# Sequencer-V02-025.net
KiCad netlist of a schematic drawn in EAGLE
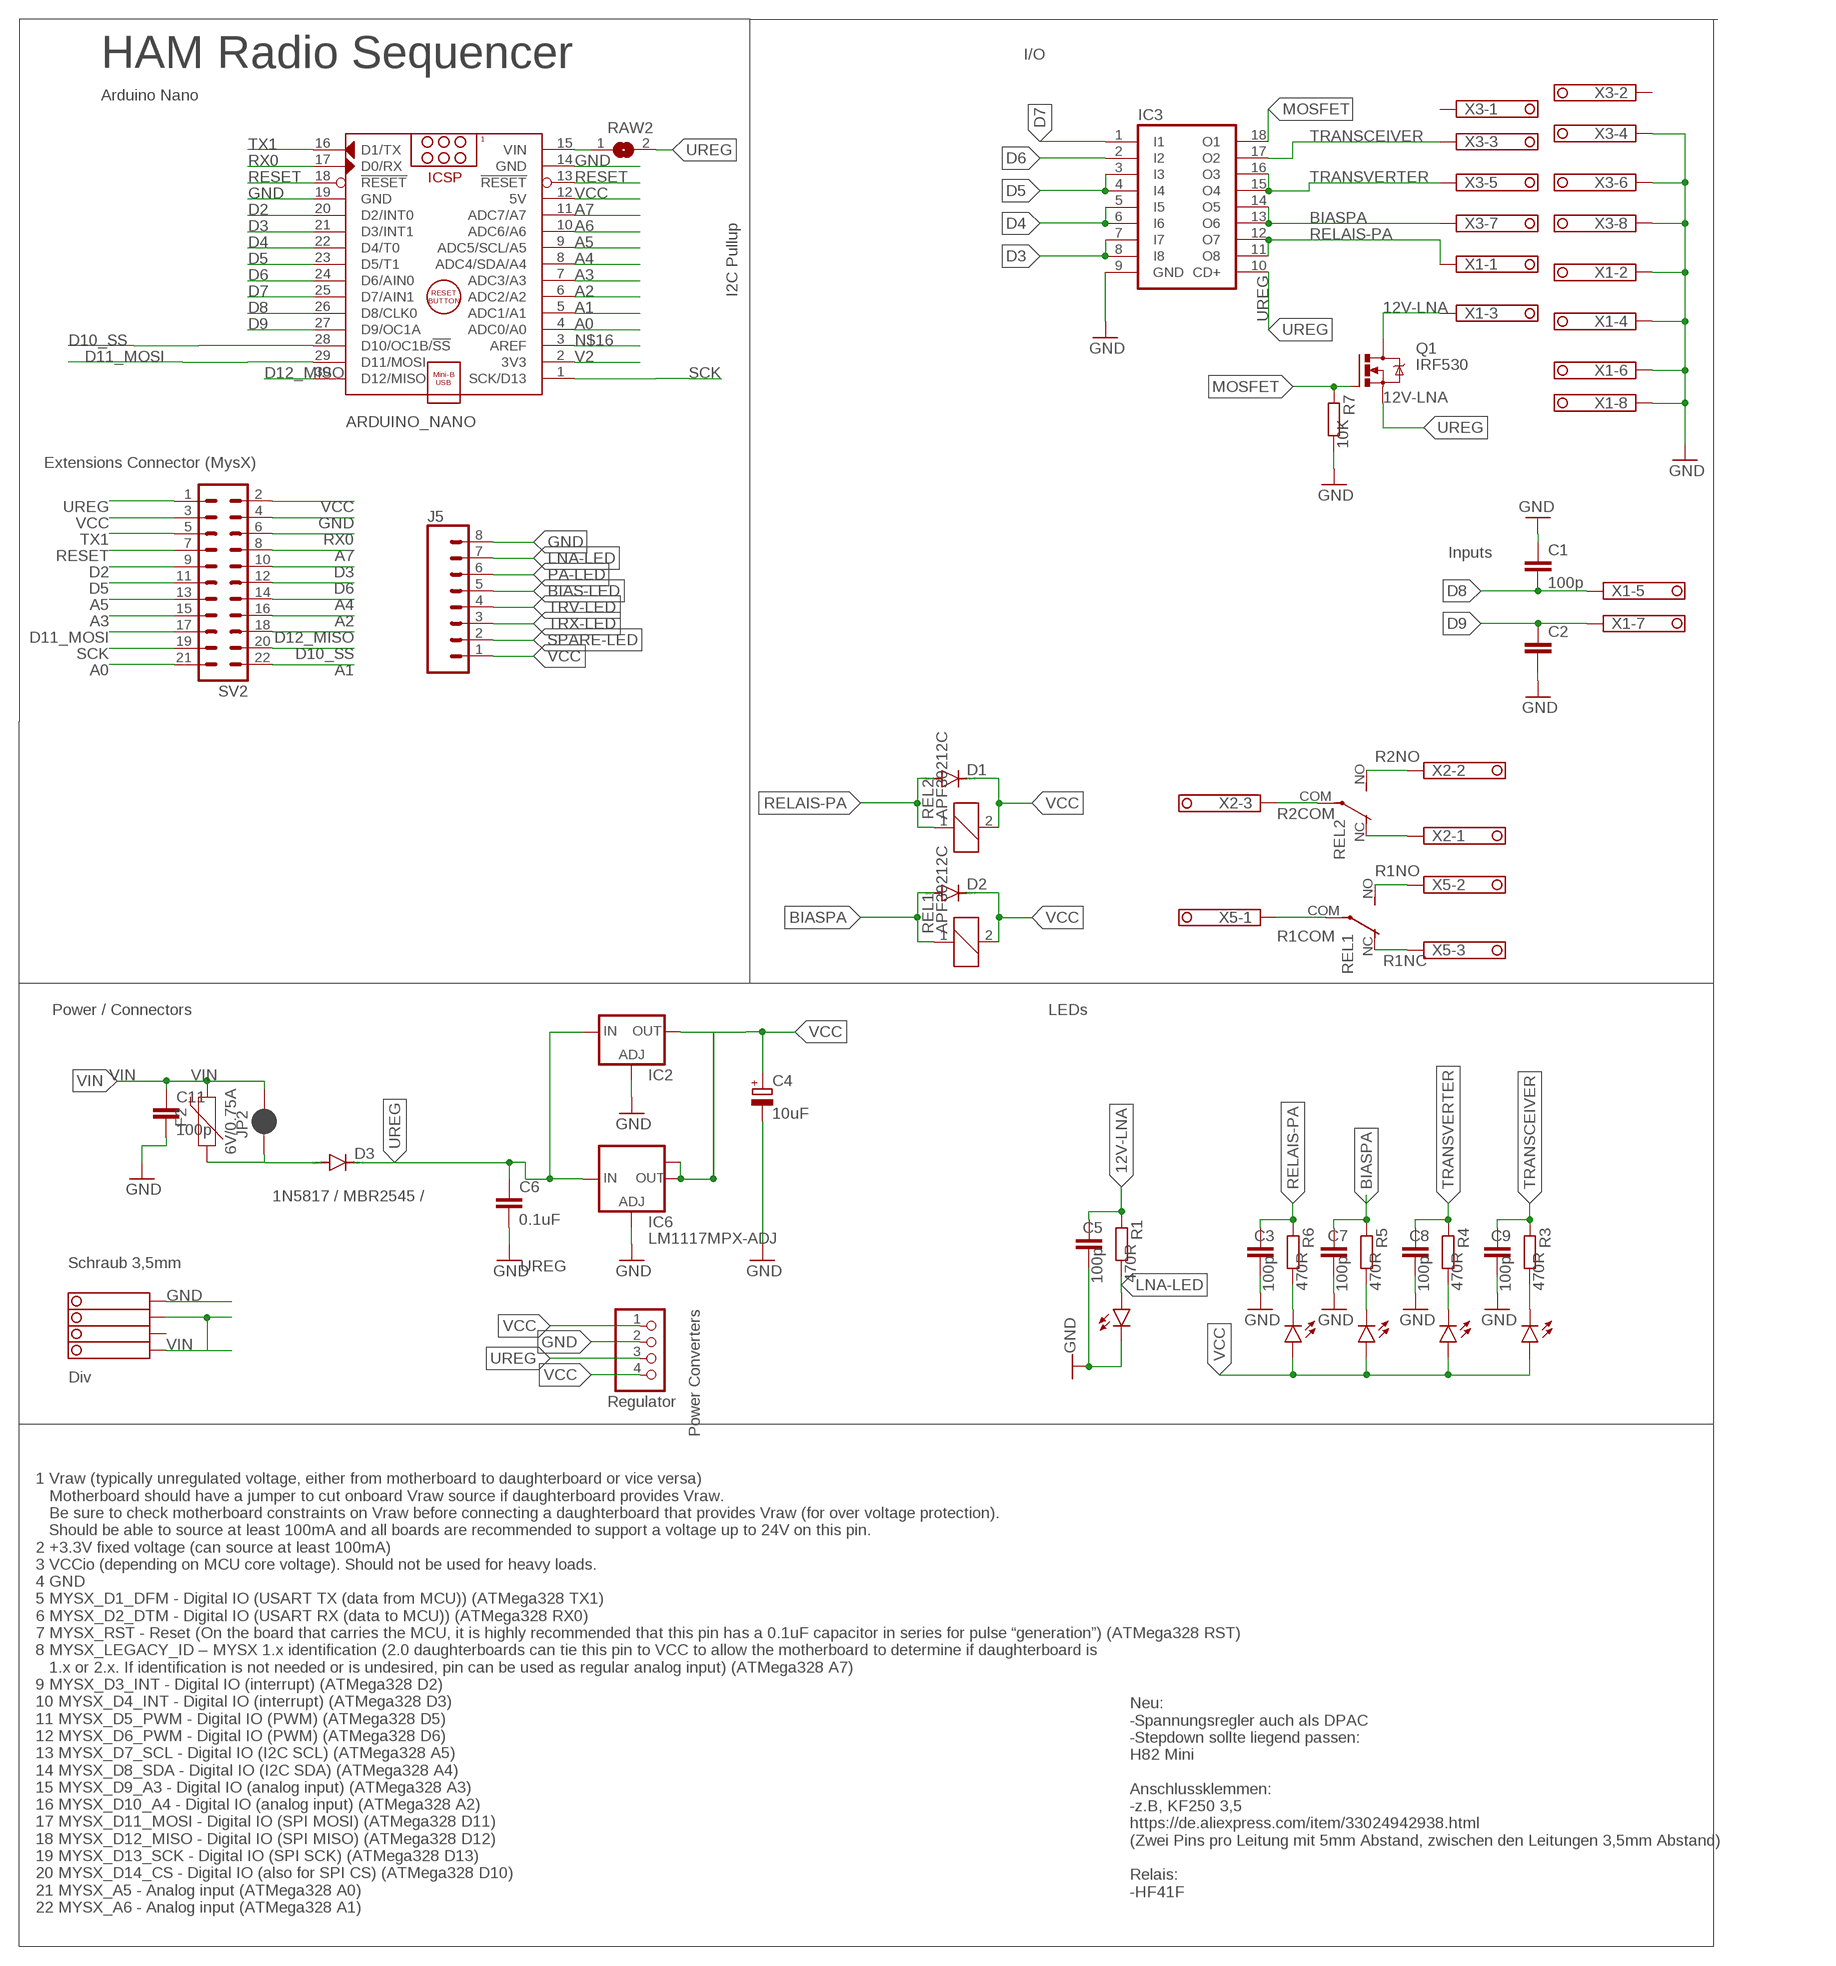
[diagram p0: schematic, sheet 1]

(export (version "E")
  (design (tool "Eeschema 10.0.6"))
  (components
    (comp (ref "ARDUINO_NANO")
      (value "ARDUINO_NANO_OHNE-BOHR")
      (footprint "eagle-import:ARDUINO_NANO")
      (libsource (lib "eagle-import") (part "ARDUINO_NANO_OHNE-BOHR"))
    )
    (comp (ref "C1")
      (value "100p")
      (footprint "eagle-import:C025-025X050")
      (libsource (lib "eagle-import") (part "C-EU025-025X050"))
    )
    (comp (ref "C2")
      (value "C-EU025-025X050")
      (footprint "eagle-import:C025-025X050")
      (libsource (lib "eagle-import") (part "C-EU025-025X050"))
    )
    (comp (ref "C3")
      (value "100p")
      (footprint "eagle-import:C025-025X050")
      (libsource (lib "eagle-import") (part "C-EU025-025X050"))
    )
    (comp (ref "C4")
      (value "10uF")
      (footprint "eagle-import:E3,5-8")
      (libsource (lib "eagle-import") (part "CPOL-EUE3.5-8"))
    )
    (comp (ref "C5")
      (value "100p")
      (footprint "eagle-import:C025-025X050")
      (libsource (lib "eagle-import") (part "C-EU025-025X050"))
    )
    (comp (ref "C6")
      (value "0.1uF")
      (footprint "eagle-import:C050-024X044")
      (libsource (lib "eagle-import") (part "C-EU050-024X044"))
    )
    (comp (ref "C7")
      (value "100p")
      (footprint "eagle-import:C025-025X050")
      (libsource (lib "eagle-import") (part "C-EU025-025X050"))
    )
    (comp (ref "C8")
      (value "100p")
      (footprint "eagle-import:C025-025X050")
      (libsource (lib "eagle-import") (part "C-EU025-025X050"))
    )
    (comp (ref "C9")
      (value "100p")
      (footprint "eagle-import:C025-025X050")
      (libsource (lib "eagle-import") (part "C-EU025-025X050"))
    )
    (comp (ref "C11")
      (value "100p")
      (footprint "eagle-import:C025-025X050")
      (libsource (lib "eagle-import") (part "C-EU025-025X050"))
    )
    (comp (ref "D1")
      (value "DIODE-D-2.5")
      (footprint "eagle-import:D-2.5")
      (libsource (lib "eagle-import") (part "DIODE-D-2.5"))
    )
    (comp (ref "D2")
      (value "DIODE-D-2.5")
      (footprint "eagle-import:D-2.5")
      (libsource (lib "eagle-import") (part "DIODE-D-2.5"))
    )
    (comp (ref "D3")
      (value "1N5817 / MBR2545 /")
      (footprint "eagle-import:D-7.5")
      (libsource (lib "eagle-import") (part "DIODE-D-7.5"))
    )
    (comp (ref "F2")
      (value "6V/0.75A")
      (footprint "eagle-import:1206")
      (libsource (lib "eagle-import") (part "PPTC_THREE-QUARTER-AMP"))
    )
    (comp (ref "IC2")
      (value "LD117ADT50TR")
      (footprint "eagle-import:DPACK")
      (libsource (lib "eagle-import") (part "LD117A?DT50TR"))
    )
    (comp (ref "IC3")
      (value "ULN2803A")
      (footprint "eagle-import:DIL18")
      (libsource (lib "eagle-import") (part "ULN2803A"))
    )
    (comp (ref "IC6")
      (value "LM1117MPX-ADJ")
      (footprint "eagle-import:SOT223")
      (libsource (lib "eagle-import") (part "LM1117MPX-ADJ"))
    )
    (comp (ref "J5")
      (value "CONN_08LOCK")
      (footprint "eagle-import:1X08_LOCK")
      (libsource (lib "eagle-import") (part "CONN_08LOCK"))
    )
    (comp (ref "JP2")
      (value "JUMPER-SMT_2_NC_PASTE_NO-SILK")
      (footprint "eagle-import:SMT-JUMPER_2_NC_PASTE_NO-SILK")
      (libsource (lib "eagle-import") (part "JUMPER-SMT_2_NC_PASTE_NO-SILK"))
    )
    (comp (ref "LED-BIAS")
      (value "LED3MM")
      (footprint "eagle-import:LED3MM")
      (libsource (lib "eagle-import") (part "LED3MM"))
    )
    (comp (ref "LED-LNA")
      (value "LED3MM")
      (footprint "eagle-import:LED3MM")
      (libsource (lib "eagle-import") (part "LED3MM"))
    )
    (comp (ref "LED-PA")
      (value "LED3MM")
      (footprint "eagle-import:LED3MM")
      (libsource (lib "eagle-import") (part "LED3MM"))
    )
    (comp (ref "LED-TRV")
      (value "LED3MM")
      (footprint "eagle-import:LED3MM")
      (libsource (lib "eagle-import") (part "LED3MM"))
    )
    (comp (ref "LED-TRX")
      (value "LED3MM")
      (footprint "eagle-import:LED3MM")
      (libsource (lib "eagle-import") (part "LED3MM"))
    )
    (comp (ref "Q1")
      (value "IRF530")
      (footprint "eagle-import:TO220BV")
      (libsource (lib "eagle-import") (part "IRF530"))
    )
    (comp (ref "R1")
      (value "470R")
      (footprint "eagle-import:0207_7")
      (libsource (lib "eagle-import") (part "R-EU_0207/7"))
    )
    (comp (ref "R3")
      (value "470R")
      (footprint "eagle-import:0207_7")
      (libsource (lib "eagle-import") (part "R-EU_0207/7"))
    )
    (comp (ref "R4")
      (value "470R")
      (footprint "eagle-import:0207_7")
      (libsource (lib "eagle-import") (part "R-EU_0207/7"))
    )
    (comp (ref "R5")
      (value "470R")
      (footprint "eagle-import:0207_7")
      (libsource (lib "eagle-import") (part "R-EU_0207/7"))
    )
    (comp (ref "R6")
      (value "470R")
      (footprint "eagle-import:0207_7")
      (libsource (lib "eagle-import") (part "R-EU_0207/7"))
    )
    (comp (ref "R7")
      (value "10K")
      (footprint "eagle-import:0207_7")
      (libsource (lib "eagle-import") (part "R-EU_0207/7"))
    )
    (comp (ref "RAW2")
      (value "SJ")
      (footprint "eagle-import:SJ")
      (libsource (lib "eagle-import") (part "SJ"))
    )
    (comp (ref "REL1")
      (value "APF30212C")
      (footprint "eagle-import:APF30212C")
      (libsource (lib "eagle-import") (part "APF30212C"))
    )
    (comp (ref "REL2")
      (value "APF30212C")
      (footprint "eagle-import:APF30212C")
      (libsource (lib "eagle-import") (part "APF30212C"))
    )
    (comp (ref "STEPDWN")
      (value "PINHD-1X04_2.54-S")
      (footprint "eagle-import:1X04-S")
      (libsource (lib "eagle-import") (part "PINHD-1X04_2.54-S"))
    )
    (comp (ref "SV2")
      (value "MA11-2")
      (footprint "eagle-import:MA11-2")
      (libsource (lib "eagle-import") (part "MA11-2"))
    )
    (comp (ref "X1")
      (value "MARTIN8X2-1751303")
      (footprint "eagle-import:1751303")
      (libsource (lib "eagle-import") (part "MARTIN8X2-1751303"))
    )
    (comp (ref "X2")
      (value "MARTIN3X2-1751303175L303-3")
      (footprint "eagle-import:1751303-3")
      (libsource (lib "eagle-import") (part "MARTIN3X2-1751303175L303-3"))
    )
    (comp (ref "X3")
      (value "MARTIN8X2-1751303")
      (footprint "eagle-import:1751303")
      (libsource (lib "eagle-import") (part "MARTIN8X2-1751303"))
    )
    (comp (ref "X4")
      (value "1751264")
      (footprint "eagle-import:1751264")
      (libsource (lib "eagle-import") (part "1751264"))
    )
    (comp (ref "X5")
      (value "MARTIN3X2-1751303175L303-3")
      (footprint "eagle-import:1751303-3")
      (libsource (lib "eagle-import") (part "MARTIN3X2-1751303175L303-3"))
    )
  )
  (nets
    (net (code "1") (name "/A0") (class "Default")
      (node (ref "ARDUINO_NANO") (pin "4") (pinfunction "ADC0/A0_4") (pintype "bidirectional"))
      (node (ref "SV2") (pin "21") (pinfunction "21_21") (pintype "passive"))
    )
    (net (code "2") (name "/A1") (class "Default")
      (node (ref "ARDUINO_NANO") (pin "5") (pinfunction "ADC1/A1_5") (pintype "bidirectional"))
      (node (ref "SV2") (pin "22") (pinfunction "22_22") (pintype "passive"))
    )
    (net (code "3") (name "/A2") (class "Default")
      (node (ref "ARDUINO_NANO") (pin "6") (pinfunction "ADC2/A2_6") (pintype "bidirectional"))
      (node (ref "SV2") (pin "16") (pinfunction "16_16") (pintype "passive"))
    )
    (net (code "4") (name "/A3") (class "Default")
      (node (ref "ARDUINO_NANO") (pin "7") (pinfunction "ADC3/A3_7") (pintype "bidirectional"))
      (node (ref "SV2") (pin "15") (pinfunction "15_15") (pintype "passive"))
    )
    (net (code "5") (name "/A4") (class "Default")
      (node (ref "ARDUINO_NANO") (pin "8") (pinfunction "ADC4/SDA/A4_8") (pintype "bidirectional"))
      (node (ref "SV2") (pin "14") (pinfunction "14_14") (pintype "passive"))
    )
    (net (code "6") (name "/A5") (class "Default")
      (node (ref "ARDUINO_NANO") (pin "9") (pinfunction "ADC5/SCL/A5_9") (pintype "bidirectional"))
      (node (ref "SV2") (pin "13") (pinfunction "13_13") (pintype "passive"))
    )
    (net (code "7") (name "/A6") (class "Default")
      (node (ref "ARDUINO_NANO") (pin "10") (pinfunction "ADC6/A6_10") (pintype "bidirectional"))
    )
    (net (code "8") (name "/A7") (class "Default")
      (node (ref "ARDUINO_NANO") (pin "11") (pinfunction "ADC7/A7_11") (pintype "bidirectional"))
      (node (ref "SV2") (pin "8") (pinfunction "8_8") (pintype "passive"))
    )
    (net (code "9") (name "/D2") (class "Default")
      (node (ref "ARDUINO_NANO") (pin "20") (pinfunction "D2/INT0_20") (pintype "bidirectional"))
      (node (ref "SV2") (pin "9") (pinfunction "9_9") (pintype "passive"))
    )
    (net (code "10") (name "/D10_SS") (class "Default")
      (node (ref "ARDUINO_NANO") (pin "28") (pinfunction "D10/OC1B/~{SS}_28") (pintype "bidirectional"))
      (node (ref "SV2") (pin "20") (pinfunction "20_20") (pintype "passive"))
    )
    (net (code "11") (name "/D11_MOSI") (class "Default")
      (node (ref "ARDUINO_NANO") (pin "29") (pinfunction "D11/MOSI_29") (pintype "bidirectional"))
      (node (ref "SV2") (pin "17") (pinfunction "17_17") (pintype "passive"))
    )
    (net (code "12") (name "/D12_MISO") (class "Default")
      (node (ref "ARDUINO_NANO") (pin "30") (pinfunction "D12/MISO_30") (pintype "bidirectional"))
      (node (ref "SV2") (pin "18") (pinfunction "18_18") (pintype "passive"))
    )
    (net (code "13") (name "/N$16") (class "Default")
      (node (ref "ARDUINO_NANO") (pin "3") (pinfunction "AREF_3") (pintype "input"))
    )
    (net (code "14") (name "/R1COM") (class "Default")
      (node (ref "REL1") (pin "COM") (pinfunction "P_COM") (pintype "passive"))
      (node (ref "X5") (pin "1") (pinfunction "K_1") (pintype "passive"))
    )
    (net (code "15") (name "/R1NC") (class "Default")
      (node (ref "REL1") (pin "NC") (pinfunction "O_NC") (pintype "passive"))
      (node (ref "X5") (pin "3") (pinfunction "K_3") (pintype "passive"))
    )
    (net (code "16") (name "/R1NO") (class "Default")
      (node (ref "REL1") (pin "NO") (pinfunction "S_NO") (pintype "passive"))
      (node (ref "X5") (pin "2") (pinfunction "K_2") (pintype "passive"))
    )
    (net (code "17") (name "/R2COM") (class "Default")
      (node (ref "REL2") (pin "COM") (pinfunction "P_COM") (pintype "passive"))
      (node (ref "X2") (pin "3") (pinfunction "K_3") (pintype "passive"))
    )
    (net (code "18") (name "/R2NO") (class "Default")
      (node (ref "REL2") (pin "NO") (pinfunction "S_NO") (pintype "passive"))
      (node (ref "X2") (pin "2") (pinfunction "K_2") (pintype "passive"))
    )
    (net (code "19") (name "/RESET") (class "Default")
      (node (ref "ARDUINO_NANO") (pin "13") (pinfunction "~{RESET}_13") (pintype "input"))
      (node (ref "ARDUINO_NANO") (pin "18") (pinfunction "~{RESET}_18") (pintype "input"))
      (node (ref "SV2") (pin "7") (pinfunction "7_7") (pintype "passive"))
    )
    (net (code "20") (name "/RX0") (class "Default")
      (node (ref "ARDUINO_NANO") (pin "17") (pinfunction "D0/RX_17") (pintype "bidirectional"))
      (node (ref "SV2") (pin "6") (pinfunction "6_6") (pintype "passive"))
    )
    (net (code "21") (name "/SCK") (class "Default")
      (node (ref "ARDUINO_NANO") (pin "1") (pinfunction "SCK/D13_1") (pintype "bidirectional"))
      (node (ref "SV2") (pin "19") (pinfunction "19_19") (pintype "passive"))
    )
    (net (code "22") (name "/TX1") (class "Default")
      (node (ref "ARDUINO_NANO") (pin "16") (pinfunction "D1/TX_16") (pintype "bidirectional"))
      (node (ref "SV2") (pin "5") (pinfunction "5_5") (pintype "passive"))
    )
    (net (code "23") (name "/V2") (class "Default")
      (node (ref "ARDUINO_NANO") (pin "2") (pinfunction "3V3_2") (pintype "output"))
    )
    (net (code "24") (name "12V-LNA") (class "Default")
      (node (ref "C5") (pin "1") (pinfunction "1_1") (pintype "passive"))
      (node (ref "Q1") (pin "D") (pinfunction "D_D") (pintype "passive"))
      (node (ref "R1") (pin "1") (pinfunction "1_1") (pintype "passive"))
      (node (ref "X1") (pin "11") (pinfunction "K_11") (pintype "passive"))
    )
    (net (code "25") (name "BIAS-LED") (class "Default")
      (node (ref "J5") (pin "5") (pinfunction "5_5") (pintype "passive"))
      (node (ref "LED-BIAS") (pin "K") (pinfunction "C_K") (pintype "passive"))
      (node (ref "R5") (pin "2") (pinfunction "2_2") (pintype "passive"))
    )
    (net (code "26") (name "BIASPA") (class "Default")
      (node (ref "C7") (pin "1") (pinfunction "1_1") (pintype "passive"))
      (node (ref "D2") (pin "A") (pinfunction "A_A") (pintype "passive"))
      (node (ref "IC3") (pin "13") (pinfunction "O6_13") (pintype "open_collector"))
      (node (ref "IC3") (pin "14") (pinfunction "O5_14") (pintype "open_collector"))
      (node (ref "R5") (pin "1") (pinfunction "1_1") (pintype "passive"))
      (node (ref "REL1") (pin "1") (pinfunction "1_1") (pintype "passive"))
      (node (ref "X3") (pin "15") (pinfunction "K_15") (pintype "passive"))
    )
    (net (code "27") (name "D3") (class "Default")
      (node (ref "ARDUINO_NANO") (pin "21") (pinfunction "D3/INT1_21") (pintype "bidirectional"))
      (node (ref "IC3") (pin "7") (pinfunction "I7_7") (pintype "input"))
      (node (ref "IC3") (pin "8") (pinfunction "I8_8") (pintype "input"))
      (node (ref "SV2") (pin "10") (pinfunction "10_10") (pintype "passive"))
    )
    (net (code "28") (name "D4") (class "Default")
      (node (ref "ARDUINO_NANO") (pin "22") (pinfunction "D4/T0_22") (pintype "bidirectional"))
      (node (ref "IC3") (pin "5") (pinfunction "I5_5") (pintype "input"))
      (node (ref "IC3") (pin "6") (pinfunction "I6_6") (pintype "input"))
    )
    (net (code "29") (name "D5") (class "Default")
      (node (ref "ARDUINO_NANO") (pin "23") (pinfunction "D5/T1_23") (pintype "bidirectional"))
      (node (ref "IC3") (pin "3") (pinfunction "I3_3") (pintype "input"))
      (node (ref "IC3") (pin "4") (pinfunction "I4_4") (pintype "input"))
      (node (ref "SV2") (pin "11") (pinfunction "11_11") (pintype "passive"))
    )
    (net (code "30") (name "D6") (class "Default")
      (node (ref "ARDUINO_NANO") (pin "24") (pinfunction "D6/AIN0_24") (pintype "bidirectional"))
      (node (ref "IC3") (pin "2") (pinfunction "I2_2") (pintype "input"))
      (node (ref "SV2") (pin "12") (pinfunction "12_12") (pintype "passive"))
    )
    (net (code "31") (name "D7") (class "Default")
      (node (ref "ARDUINO_NANO") (pin "25") (pinfunction "D7/AIN1_25") (pintype "bidirectional"))
      (node (ref "IC3") (pin "1") (pinfunction "I1_1") (pintype "input"))
    )
    (net (code "32") (name "D8") (class "Default")
      (node (ref "ARDUINO_NANO") (pin "26") (pinfunction "D8/CLK0_26") (pintype "bidirectional"))
      (node (ref "C1") (pin "2") (pinfunction "2_2") (pintype "passive"))
      (node (ref "X1") (pin "13") (pinfunction "K_13") (pintype "passive"))
    )
    (net (code "33") (name "D9") (class "Default")
      (node (ref "ARDUINO_NANO") (pin "27") (pinfunction "D9/OC1A_27") (pintype "bidirectional"))
      (node (ref "C2") (pin "1") (pinfunction "1_1") (pintype "passive"))
      (node (ref "X1") (pin "15") (pinfunction "K_15") (pintype "passive"))
    )
    (net (code "34") (name "GND") (class "Default")
      (node (ref "ARDUINO_NANO") (pin "14") (pinfunction "GND_14") (pintype "power_in"))
      (node (ref "ARDUINO_NANO") (pin "19") (pinfunction "GND_19") (pintype "power_in"))
      (node (ref "C1") (pin "1") (pinfunction "1_1") (pintype "passive"))
      (node (ref "C11") (pin "2") (pinfunction "2_2") (pintype "passive"))
      (node (ref "C2") (pin "2") (pinfunction "2_2") (pintype "passive"))
      (node (ref "C3") (pin "2") (pinfunction "2_2") (pintype "passive"))
      (node (ref "C4") (pin "-") (pinfunction "-_-") (pintype "passive"))
      (node (ref "C5") (pin "2") (pinfunction "2_2") (pintype "passive"))
      (node (ref "C6") (pin "2") (pinfunction "2_2") (pintype "passive"))
      (node (ref "C7") (pin "2") (pinfunction "2_2") (pintype "passive"))
      (node (ref "C8") (pin "2") (pinfunction "2_2") (pintype "passive"))
      (node (ref "C9") (pin "2") (pinfunction "2_2") (pintype "passive"))
      (node (ref "IC2") (pin "1") (pinfunction "ADJ_1") (pintype "input"))
      (node (ref "IC3") (pin "9") (pinfunction "GND_9") (pintype "power_in"))
      (node (ref "IC6") (pin "1") (pinfunction "ADJ_1") (pintype "input"))
      (node (ref "J5") (pin "8") (pinfunction "8_8") (pintype "passive"))
      (node (ref "LED-LNA") (pin "K") (pinfunction "C_K") (pintype "passive"))
      (node (ref "R7") (pin "2") (pinfunction "2_2") (pintype "passive"))
      (node (ref "STEPDWN") (pin "2") (pinfunction "2_2") (pintype "passive"))
      (node (ref "SV2") (pin "4") (pinfunction "4_4") (pintype "passive"))
      (node (ref "X1") (pin "10") (pinfunction "K_10") (pintype "passive"))
      (node (ref "X1") (pin "12") (pinfunction "K_12") (pintype "passive"))
      (node (ref "X1") (pin "14") (pinfunction "K_14") (pintype "passive"))
      (node (ref "X1") (pin "16") (pinfunction "K_16") (pintype "passive"))
      (node (ref "X3") (pin "12") (pinfunction "K_12") (pintype "passive"))
      (node (ref "X3") (pin "14") (pinfunction "K_14") (pintype "passive"))
      (node (ref "X3") (pin "16") (pinfunction "K_16") (pintype "passive"))
      (node (ref "X4") (pin "4") (pinfunction "K_4") (pintype "passive"))
    )
    (net (code "35") (name "LNA-LED") (class "Default")
      (node (ref "J5") (pin "7") (pinfunction "7_7") (pintype "passive"))
      (node (ref "LED-LNA") (pin "A") (pinfunction "A_A") (pintype "passive"))
      (node (ref "R1") (pin "2") (pinfunction "2_2") (pintype "passive"))
    )
    (net (code "36") (name "MOSFET") (class "Default")
      (node (ref "IC3") (pin "18") (pinfunction "O1_18") (pintype "open_collector"))
      (node (ref "Q1") (pin "G") (pinfunction "G_G") (pintype "passive"))
      (node (ref "R7") (pin "1") (pinfunction "1_1") (pintype "passive"))
    )
    (net (code "37") (name "Net-(ARDUINO_NANO-VIN)") (class "Default")
      (node (ref "ARDUINO_NANO") (pin "15") (pinfunction "VIN_15") (pintype "power_in"))
      (node (ref "RAW2") (pin "1") (pinfunction "1_1") (pintype "passive"))
    )
    (net (code "38") (name "Net-(D3-PadA)") (class "Default")
      (node (ref "D3") (pin "A") (pinfunction "A_A") (pintype "passive"))
      (node (ref "F2") (pin "1") (pinfunction "1_1") (pintype "bidirectional"))
      (node (ref "JP2") (pin "1") (pinfunction "1_1") (pintype "passive"))
    )
    (net (code "39") (name "Net-(REL2B-O)") (class "Default")
      (node (ref "REL2") (pin "NC") (pinfunction "O_NC") (pintype "passive"))
      (node (ref "X2") (pin "1") (pinfunction "K_1") (pintype "passive"))
    )
    (net (code "40") (name "PA-LED") (class "Default")
      (node (ref "J5") (pin "6") (pinfunction "6_6") (pintype "passive"))
      (node (ref "LED-PA") (pin "K") (pinfunction "C_K") (pintype "passive"))
      (node (ref "R6") (pin "2") (pinfunction "2_2") (pintype "passive"))
    )
    (net (code "41") (name "RELAIS-PA") (class "Default")
      (node (ref "C3") (pin "1") (pinfunction "1_1") (pintype "passive"))
      (node (ref "D1") (pin "A") (pinfunction "A_A") (pintype "passive"))
      (node (ref "IC3") (pin "11") (pinfunction "O8_11") (pintype "open_collector"))
      (node (ref "IC3") (pin "12") (pinfunction "O7_12") (pintype "open_collector"))
      (node (ref "R6") (pin "1") (pinfunction "1_1") (pintype "passive"))
      (node (ref "REL2") (pin "1") (pinfunction "1_1") (pintype "passive"))
      (node (ref "X1") (pin "9") (pinfunction "K_9") (pintype "passive"))
    )
    (net (code "42") (name "SPARE-LED") (class "Default")
      (node (ref "J5") (pin "2") (pinfunction "2_2") (pintype "passive"))
    )
    (net (code "43") (name "TRANSCEIVER") (class "Default")
      (node (ref "C9") (pin "1") (pinfunction "1_1") (pintype "passive"))
      (node (ref "IC3") (pin "17") (pinfunction "O2_17") (pintype "open_collector"))
      (node (ref "R3") (pin "1") (pinfunction "1_1") (pintype "passive"))
      (node (ref "X3") (pin "11") (pinfunction "K_11") (pintype "passive"))
    )
    (net (code "44") (name "TRANSVERTER") (class "Default")
      (node (ref "C8") (pin "1") (pinfunction "1_1") (pintype "passive"))
      (node (ref "IC3") (pin "15") (pinfunction "O4_15") (pintype "open_collector"))
      (node (ref "IC3") (pin "16") (pinfunction "O3_16") (pintype "open_collector"))
      (node (ref "R4") (pin "1") (pinfunction "1_1") (pintype "passive"))
      (node (ref "X3") (pin "13") (pinfunction "K_13") (pintype "passive"))
    )
    (net (code "45") (name "TRV-LED") (class "Default")
      (node (ref "J5") (pin "4") (pinfunction "4_4") (pintype "passive"))
      (node (ref "LED-TRV") (pin "K") (pinfunction "C_K") (pintype "passive"))
      (node (ref "R4") (pin "2") (pinfunction "2_2") (pintype "passive"))
    )
    (net (code "46") (name "TRX-LED") (class "Default")
      (node (ref "J5") (pin "3") (pinfunction "3_3") (pintype "passive"))
      (node (ref "LED-TRX") (pin "K") (pinfunction "C_K") (pintype "passive"))
      (node (ref "R3") (pin "2") (pinfunction "2_2") (pintype "passive"))
    )
    (net (code "47") (name "UREG") (class "Default")
      (node (ref "C6") (pin "1") (pinfunction "1_1") (pintype "passive"))
      (node (ref "D3") (pin "C") (pinfunction "C_C") (pintype "passive"))
      (node (ref "IC2") (pin "3") (pinfunction "IN_3") (pintype "input"))
      (node (ref "IC3") (pin "10") (pinfunction "CD+_10") (pintype "passive"))
      (node (ref "IC6") (pin "3") (pinfunction "IN_3") (pintype "input"))
      (node (ref "Q1") (pin "S") (pinfunction "S_S") (pintype "passive"))
      (node (ref "RAW2") (pin "2") (pinfunction "2_2") (pintype "passive"))
      (node (ref "STEPDWN") (pin "3") (pinfunction "3_3") (pintype "passive"))
      (node (ref "SV2") (pin "1") (pinfunction "1_1") (pintype "passive"))
    )
    (net (code "48") (name "VCC") (class "Default")
      (node (ref "ARDUINO_NANO") (pin "12") (pinfunction "5V_12") (pintype "power_in"))
      (node (ref "C4") (pin "+") (pinfunction "+_+") (pintype "passive"))
      (node (ref "D1") (pin "C") (pinfunction "C_C") (pintype "passive"))
      (node (ref "D2") (pin "C") (pinfunction "C_C") (pintype "passive"))
      (node (ref "IC2") (pin "4") (pinfunction "OUT_4") (pintype "passive"))
      (node (ref "IC6") (pin "2") (pinfunction "OUT_2") (pintype "passive"))
      (node (ref "IC6") (pin "TAB") (pinfunction "OUT1_TAB") (pintype "passive"))
      (node (ref "J5") (pin "1") (pinfunction "1_1") (pintype "passive"))
      (node (ref "LED-BIAS") (pin "A") (pinfunction "A_A") (pintype "passive"))
      (node (ref "LED-PA") (pin "A") (pinfunction "A_A") (pintype "passive"))
      (node (ref "LED-TRV") (pin "A") (pinfunction "A_A") (pintype "passive"))
      (node (ref "LED-TRX") (pin "A") (pinfunction "A_A") (pintype "passive"))
      (node (ref "REL1") (pin "2") (pinfunction "2_2") (pintype "passive"))
      (node (ref "REL2") (pin "2") (pinfunction "2_2") (pintype "passive"))
      (node (ref "STEPDWN") (pin "1") (pinfunction "1_1") (pintype "passive"))
      (node (ref "STEPDWN") (pin "4") (pinfunction "4_4") (pintype "passive"))
      (node (ref "SV2") (pin "2") (pinfunction "2_2") (pintype "passive"))
      (node (ref "SV2") (pin "3") (pinfunction "3_3") (pintype "passive"))
    )
    (net (code "49") (name "VIN") (class "Default")
      (node (ref "C11") (pin "1") (pinfunction "1_1") (pintype "passive"))
      (node (ref "F2") (pin "2") (pinfunction "2_2") (pintype "bidirectional"))
      (node (ref "JP2") (pin "2") (pinfunction "2_2") (pintype "passive"))
      (node (ref "X4") (pin "1") (pinfunction "K_1") (pintype "passive"))
      (node (ref "X4") (pin "3") (pinfunction "K_3") (pintype "passive"))
    )
    (net (code "50") (name "unconnected-(X3A-K-Pad9)") (class "Default")
      (node (ref "X3") (pin "9") (pinfunction "K_9") (pintype "passive"))
    )
    (net (code "51") (name "unconnected-(X3B-K-Pad10)") (class "Default")
      (node (ref "X3") (pin "10") (pinfunction "K_10") (pintype "passive"))
    )
    (net (code "52") (name "unconnected-(X4B-K-Pad2)") (class "Default")
      (node (ref "X4") (pin "2") (pinfunction "K_2") (pintype "passive"))
    )
  )
)
